# 1_USB.net
KiCad netlist of a schematic drawn in Altium Designer
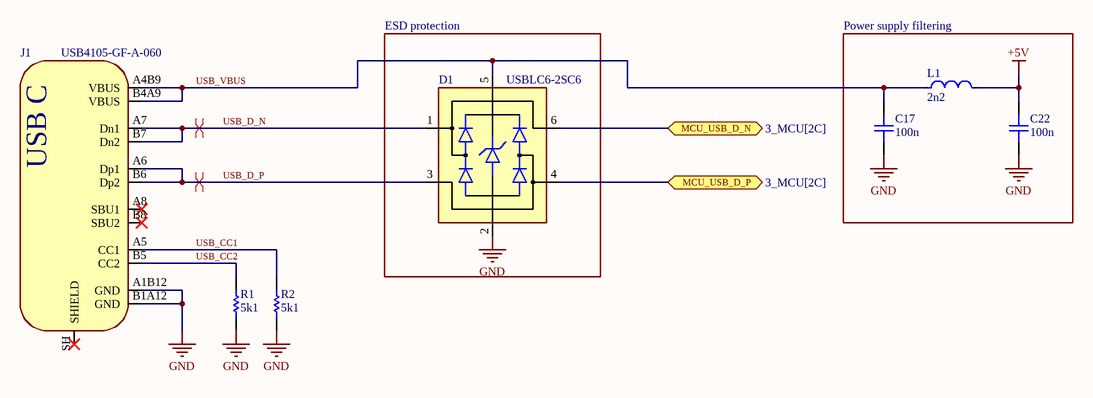
[diagram p0: 1_USB.SchDoc]

(export (version "E")
  (design (tool "Eeschema 10.0.6"))
  (components
    (comp (ref "C17")
      (value "100n")
      (footprint "CAP_0402")
      (description "Capacitor SMD 0402 16V")
      (libsource (lib "Schematic-Lib-PhilsLab") (part "CAP_0402_16V"))
    )
    (comp (ref "C22")
      (value "100n")
      (footprint "CAP_0402")
      (description "Capacitor SMD 0402 16V")
      (libsource (lib "Schematic-Lib-PhilsLab") (part "CAP_0402_16V"))
    )
    (comp (ref "D1")
      (value "USBLC6-2SC6")
      (footprint "SOT-23-6")
      (description "Low-Capacitance ESD Protection USB")
      (fields (field (name "MANUFACTURER") "STMicroelectronics"))
      (libsource (lib "Schematic-Lib-PhilsLab") (part "USBLC6-2SC6"))
    )
    (comp (ref "J1")
      (value "USB4105-GF-A-060")
      (footprint "USB4105-GF-A-060")
      (description "USB Connector Type C SMT 12 Pin")
      (fields (field (name "MANUFACTURER") "GCT"))
      (libsource (lib "Schematic-Lib-PhilsLab") (part "USB4105-GF-A-060"))
    )
    (comp (ref "L1")
      (value "2n2")
      (footprint "FP-LQW15AN_80-MFG")
      (description "Wire Wound RF Inductor 2.2nH ±2% 2530mA 0.022Ω 0402 (1005)")
      (libsource (lib "Altium Content Vault") (part "725321dda6339637d4d059423bc1c3c"))
    )
    (comp (ref "R1")
      (value "5k1")
      (footprint "RESC1005X40X25ML10T10")
      (fields (field (name "PART NUMBER") "RK73B1ETTP512J") (field (name "MANUFACTURER") "KOA Speer"))
      (libsource (lib "Altium Content Vault") (part "RES"))
    )
    (comp (ref "R2")
      (value "5k1")
      (footprint "RESC1005X40X25ML10T10")
      (fields (field (name "PART NUMBER") "RK73B1ETTP512J") (field (name "MANUFACTURER") "KOA Speer"))
      (libsource (lib "Altium Content Vault") (part "RES"))
    )
  )
  (nets
    (net (code "1") (name "+5V") (class "Default")
      (node (ref "C22") (pin "2") (pinfunction "2_2") (pintype "passive"))
      (node (ref "L1") (pin "2") (pinfunction "2_2") (pintype "passive"))
    )
    (net (code "2") (name "/MCU_USB_D_N") (class "Default")
      (node (ref "D1") (pin "6") (pinfunction "IO1_6") (pintype "bidirectional"))
    )
    (net (code "3") (name "/MCU_USB_D_P") (class "Default")
      (node (ref "D1") (pin "4") (pinfunction "IO2_4") (pintype "bidirectional"))
    )
    (net (code "4") (name "/USB_CC1") (class "Default")
      (node (ref "J1") (pin "A5") (pinfunction "CC1_A5") (pintype "passive"))
      (node (ref "R2") (pin "1") (pinfunction "1_1") (pintype "passive"))
    )
    (net (code "5") (name "/USB_CC2") (class "Default")
      (node (ref "J1") (pin "B5") (pinfunction "CC2_B5") (pintype "passive"))
      (node (ref "R1") (pin "1") (pinfunction "1_1") (pintype "passive"))
    )
    (net (code "6") (name "/USB_D_N") (class "Default")
      (node (ref "D1") (pin "1") (pinfunction "IO1_1") (pintype "bidirectional"))
      (node (ref "J1") (pin "A7") (pinfunction "Dn1_A7") (pintype "passive"))
      (node (ref "J1") (pin "B7") (pinfunction "Dn2_B7") (pintype "passive"))
    )
    (net (code "7") (name "/USB_D_P") (class "Default")
      (node (ref "D1") (pin "3") (pinfunction "IO2_3") (pintype "bidirectional"))
      (node (ref "J1") (pin "A6") (pinfunction "Dp1_A6") (pintype "passive"))
      (node (ref "J1") (pin "B6") (pinfunction "Dp2_B6") (pintype "passive"))
    )
    (net (code "8") (name "/USB_VBUS") (class "Default")
      (node (ref "C17") (pin "2") (pinfunction "2_2") (pintype "passive"))
      (node (ref "D1") (pin "5") (pinfunction "VBUS_5") (pintype "power_in"))
      (node (ref "J1") (pin "A4B9") (pinfunction "VBUS_A4B9") (pintype "passive"))
      (node (ref "J1") (pin "B4A9") (pinfunction "VBUS_B4A9") (pintype "passive"))
      (node (ref "L1") (pin "1") (pinfunction "1_1") (pintype "passive"))
    )
    (net (code "9") (name "GND") (class "Default")
      (node (ref "C17") (pin "1") (pinfunction "1_1") (pintype "passive"))
      (node (ref "C22") (pin "1") (pinfunction "1_1") (pintype "passive"))
      (node (ref "D1") (pin "2") (pinfunction "GND_2") (pintype "power_in"))
      (node (ref "J1") (pin "A1B12") (pinfunction "GND_A1B12") (pintype "passive"))
      (node (ref "J1") (pin "B1A12") (pinfunction "GND_B1A12") (pintype "passive"))
      (node (ref "R1") (pin "2") (pinfunction "2_2") (pintype "passive"))
      (node (ref "R2") (pin "2") (pinfunction "2_2") (pintype "passive"))
    )
    (net (code "10") (name "unconnected-(J1-SBU1-PadA8)") (class "Default")
      (node (ref "J1") (pin "A8") (pinfunction "SBU1_A8") (pintype "passive+no_connect"))
    )
    (net (code "11") (name "unconnected-(J1-SBU2-PadB8)") (class "Default")
      (node (ref "J1") (pin "B8") (pinfunction "SBU2_B8") (pintype "passive+no_connect"))
    )
    (net (code "12") (name "unconnected-(J1-SHIELD-PadSH)") (class "Default")
      (node (ref "J1") (pin "SH") (pinfunction "SHIELD_SH") (pintype "passive+no_connect"))
    )
  )
)
